# motors.net
KiCad netlist of a schematic drawn in EAGLE
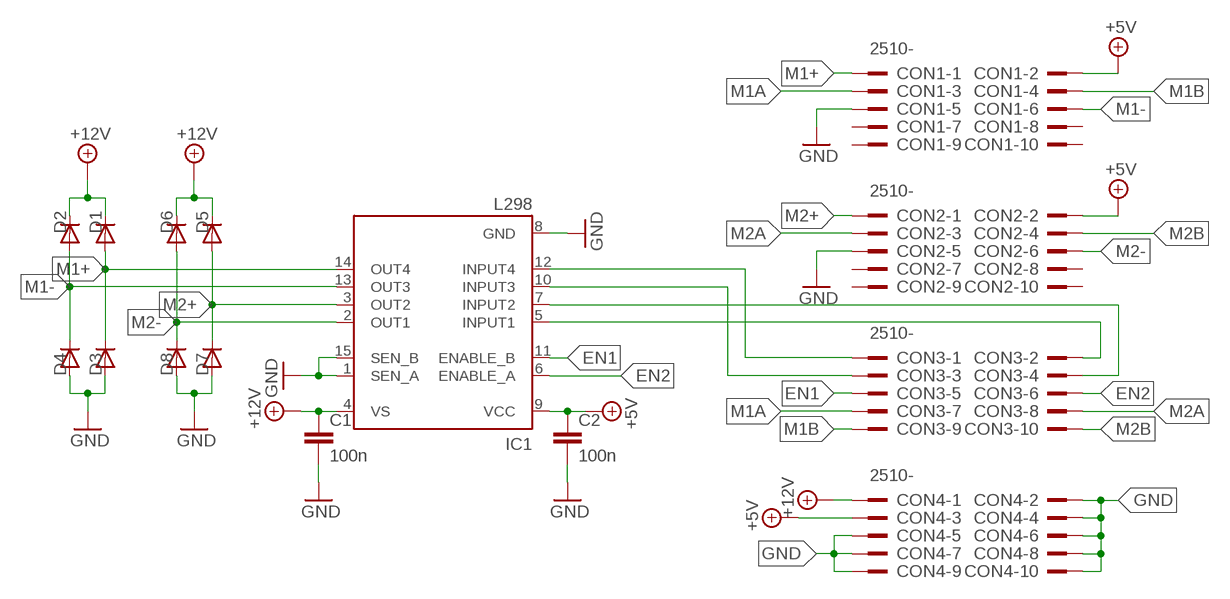
[diagram p0: schematic, sheet 1]

(export (version "E")
  (design (tool "Eeschema 10.0.6"))
  (components
    (comp (ref "C1")
      (value "100n")
      (footprint "eagle-import:C050-025X075")
      (libsource (lib "eagle-import") (part "C-EU050-025X075"))
    )
    (comp (ref "C2")
      (value "100n")
      (footprint "eagle-import:C050-025X075")
      (libsource (lib "eagle-import") (part "C-EU050-025X075"))
    )
    (comp (ref "CON1")
      (value "2510-")
      (footprint "eagle-import:PAK100_2500-10")
      (fields (field (name "MF") "3M") (field (name "MPN") "2510-6002UB"))
      (libsource (lib "eagle-import") (part "2510-"))
    )
    (comp (ref "CON2")
      (value "2510-")
      (footprint "eagle-import:PAK100_2500-10")
      (fields (field (name "MF") "3M") (field (name "MPN") "2510-6002UB"))
      (libsource (lib "eagle-import") (part "2510-"))
    )
    (comp (ref "CON3")
      (value "2510-")
      (footprint "eagle-import:PAK100_2500-10")
      (fields (field (name "MF") "3M") (field (name "MPN") "2510-6002UB"))
      (libsource (lib "eagle-import") (part "2510-"))
    )
    (comp (ref "CON4")
      (value "2510-")
      (footprint "eagle-import:PAK100_2500-10")
      (fields (field (name "MF") "3M") (field (name "MPN") "2510-6002UB"))
      (libsource (lib "eagle-import") (part "2510-"))
    )
    (comp (ref "D1")
      (value "1N4004")
      (footprint "eagle-import:DO41-10")
      (libsource (lib "eagle-import") (part "1N4004"))
    )
    (comp (ref "D2")
      (value "1N4004")
      (footprint "eagle-import:DO41-10")
      (libsource (lib "eagle-import") (part "1N4004"))
    )
    (comp (ref "D3")
      (value "1N4004")
      (footprint "eagle-import:DO41-10")
      (libsource (lib "eagle-import") (part "1N4004"))
    )
    (comp (ref "D4")
      (value "1N4004")
      (footprint "eagle-import:DO41-10")
      (libsource (lib "eagle-import") (part "1N4004"))
    )
    (comp (ref "D5")
      (value "1N4004")
      (footprint "eagle-import:DO41-10")
      (libsource (lib "eagle-import") (part "1N4004"))
    )
    (comp (ref "D6")
      (value "1N4004")
      (footprint "eagle-import:DO41-10")
      (libsource (lib "eagle-import") (part "1N4004"))
    )
    (comp (ref "D7")
      (value "1N4004")
      (footprint "eagle-import:DO41-10")
      (libsource (lib "eagle-import") (part "1N4004"))
    )
    (comp (ref "D8")
      (value "1N4004")
      (footprint "eagle-import:DO41-10")
      (libsource (lib "eagle-import") (part "1N4004"))
    )
    (comp (ref "IC1")
      (value "L298")
      (footprint "eagle-import:MULTIWATT-15")
      (fields (field (name "MPN") "L298N"))
      (libsource (lib "eagle-import") (part "L298"))
    )
  )
  (nets
    (net (code "1") (name "+5V") (class "Default")
      (node (ref "C2") (pin "1") (pinfunction "1_1") (pintype "passive"))
      (node (ref "CON1") (pin "2") (pinfunction "KL_2") (pintype "passive"))
      (node (ref "CON2") (pin "2") (pinfunction "KL_2") (pintype "passive"))
      (node (ref "CON4") (pin "3") (pinfunction "KL_3") (pintype "passive"))
      (node (ref "IC1") (pin "9") (pinfunction "VCC_9") (pintype "power_in"))
    )
    (net (code "2") (name "+12V") (class "Default")
      (node (ref "C1") (pin "1") (pinfunction "1_1") (pintype "passive"))
      (node (ref "CON4") (pin "1") (pinfunction "KL_1") (pintype "passive"))
      (node (ref "D1") (pin "C") (pinfunction "C_C") (pintype "passive"))
      (node (ref "D2") (pin "C") (pinfunction "C_C") (pintype "passive"))
      (node (ref "D5") (pin "C") (pinfunction "C_C") (pintype "passive"))
      (node (ref "D6") (pin "C") (pinfunction "C_C") (pintype "passive"))
      (node (ref "IC1") (pin "4") (pinfunction "VS_4") (pintype "power_in"))
    )
    (net (code "3") (name "EN1") (class "Default")
      (node (ref "CON3") (pin "5") (pinfunction "KL_5") (pintype "passive"))
      (node (ref "IC1") (pin "11") (pinfunction "ENABLE_B_11") (pintype "input"))
    )
    (net (code "4") (name "EN2") (class "Default")
      (node (ref "CON3") (pin "6") (pinfunction "KL_6") (pintype "passive"))
      (node (ref "IC1") (pin "6") (pinfunction "ENABLE_A_6") (pintype "input"))
    )
    (net (code "5") (name "GND") (class "Default")
      (node (ref "C1") (pin "2") (pinfunction "2_2") (pintype "passive"))
      (node (ref "C2") (pin "2") (pinfunction "2_2") (pintype "passive"))
      (node (ref "CON1") (pin "5") (pinfunction "KL_5") (pintype "passive"))
      (node (ref "CON2") (pin "5") (pinfunction "KL_5") (pintype "passive"))
      (node (ref "CON4") (pin "10") (pinfunction "KL_10") (pintype "passive"))
      (node (ref "CON4") (pin "2") (pinfunction "KL_2") (pintype "passive"))
      (node (ref "CON4") (pin "4") (pinfunction "KL_4") (pintype "passive"))
      (node (ref "CON4") (pin "5") (pinfunction "KL_5") (pintype "passive"))
      (node (ref "CON4") (pin "6") (pinfunction "KL_6") (pintype "passive"))
      (node (ref "CON4") (pin "7") (pinfunction "KL_7") (pintype "passive"))
      (node (ref "CON4") (pin "8") (pinfunction "KL_8") (pintype "passive"))
      (node (ref "CON4") (pin "9") (pinfunction "KL_9") (pintype "passive"))
      (node (ref "D3") (pin "A") (pinfunction "A_A") (pintype "passive"))
      (node (ref "D4") (pin "A") (pinfunction "A_A") (pintype "passive"))
      (node (ref "D7") (pin "A") (pinfunction "A_A") (pintype "passive"))
      (node (ref "D8") (pin "A") (pinfunction "A_A") (pintype "passive"))
      (node (ref "IC1") (pin "1") (pinfunction "SEN_A_1") (pintype "input"))
      (node (ref "IC1") (pin "15") (pinfunction "SEN_B_15") (pintype "input"))
      (node (ref "IC1") (pin "8") (pinfunction "GND_8") (pintype "power_in"))
    )
    (net (code "6") (name "M1+") (class "Default")
      (node (ref "CON1") (pin "1") (pinfunction "KL_1") (pintype "passive"))
      (node (ref "D1") (pin "A") (pinfunction "A_A") (pintype "passive"))
      (node (ref "D3") (pin "C") (pinfunction "C_C") (pintype "passive"))
      (node (ref "IC1") (pin "14") (pinfunction "OUT4_14") (pintype "output"))
    )
    (net (code "7") (name "M1-") (class "Default")
      (node (ref "CON1") (pin "6") (pinfunction "KL_6") (pintype "passive"))
      (node (ref "D2") (pin "A") (pinfunction "A_A") (pintype "passive"))
      (node (ref "D4") (pin "C") (pinfunction "C_C") (pintype "passive"))
      (node (ref "IC1") (pin "13") (pinfunction "OUT3_13") (pintype "output"))
    )
    (net (code "8") (name "M1A") (class "Default")
      (node (ref "CON1") (pin "3") (pinfunction "KL_3") (pintype "passive"))
      (node (ref "CON3") (pin "7") (pinfunction "KL_7") (pintype "passive"))
    )
    (net (code "9") (name "M1B") (class "Default")
      (node (ref "CON1") (pin "4") (pinfunction "KL_4") (pintype "passive"))
      (node (ref "CON3") (pin "9") (pinfunction "KL_9") (pintype "passive"))
    )
    (net (code "10") (name "M2+") (class "Default")
      (node (ref "CON2") (pin "1") (pinfunction "KL_1") (pintype "passive"))
      (node (ref "D5") (pin "A") (pinfunction "A_A") (pintype "passive"))
      (node (ref "D7") (pin "C") (pinfunction "C_C") (pintype "passive"))
      (node (ref "IC1") (pin "3") (pinfunction "OUT2_3") (pintype "output"))
    )
    (net (code "11") (name "M2-") (class "Default")
      (node (ref "CON2") (pin "6") (pinfunction "KL_6") (pintype "passive"))
      (node (ref "D6") (pin "A") (pinfunction "A_A") (pintype "passive"))
      (node (ref "D8") (pin "C") (pinfunction "C_C") (pintype "passive"))
      (node (ref "IC1") (pin "2") (pinfunction "OUT1_2") (pintype "output"))
    )
    (net (code "12") (name "M2A") (class "Default")
      (node (ref "CON2") (pin "3") (pinfunction "KL_3") (pintype "passive"))
      (node (ref "CON3") (pin "8") (pinfunction "KL_8") (pintype "passive"))
    )
    (net (code "13") (name "M2B") (class "Default")
      (node (ref "CON2") (pin "4") (pinfunction "KL_4") (pintype "passive"))
      (node (ref "CON3") (pin "10") (pinfunction "KL_10") (pintype "passive"))
    )
    (net (code "14") (name "Net-(CON3A-KL)") (class "Default")
      (node (ref "CON3") (pin "1") (pinfunction "KL_1") (pintype "passive"))
      (node (ref "IC1") (pin "12") (pinfunction "INPUT4_12") (pintype "input"))
    )
    (net (code "15") (name "Net-(CON3C-KL)") (class "Default")
      (node (ref "CON3") (pin "2") (pinfunction "KL_2") (pintype "passive"))
      (node (ref "IC1") (pin "5") (pinfunction "INPUT1_5") (pintype "input"))
    )
    (net (code "16") (name "Net-(CON3D-KL)") (class "Default")
      (node (ref "CON3") (pin "3") (pinfunction "KL_3") (pintype "passive"))
      (node (ref "IC1") (pin "10") (pinfunction "INPUT3_10") (pintype "input"))
    )
    (net (code "17") (name "Net-(CON3E-KL)") (class "Default")
      (node (ref "CON3") (pin "4") (pinfunction "KL_4") (pintype "passive"))
      (node (ref "IC1") (pin "7") (pinfunction "INPUT2_7") (pintype "input"))
    )
    (net (code "18") (name "unconnected-(CON1B-KL-Pad10)") (class "Default")
      (node (ref "CON1") (pin "10") (pinfunction "KL_10") (pintype "passive"))
    )
    (net (code "19") (name "unconnected-(CON1H-KL-Pad7)") (class "Default")
      (node (ref "CON1") (pin "7") (pinfunction "KL_7") (pintype "passive"))
    )
    (net (code "20") (name "unconnected-(CON1I-KL-Pad8)") (class "Default")
      (node (ref "CON1") (pin "8") (pinfunction "KL_8") (pintype "passive"))
    )
    (net (code "21") (name "unconnected-(CON1J-KL-Pad9)") (class "Default")
      (node (ref "CON1") (pin "9") (pinfunction "KL_9") (pintype "passive"))
    )
    (net (code "22") (name "unconnected-(CON2B-KL-Pad10)") (class "Default")
      (node (ref "CON2") (pin "10") (pinfunction "KL_10") (pintype "passive"))
    )
    (net (code "23") (name "unconnected-(CON2H-KL-Pad7)") (class "Default")
      (node (ref "CON2") (pin "7") (pinfunction "KL_7") (pintype "passive"))
    )
    (net (code "24") (name "unconnected-(CON2I-KL-Pad8)") (class "Default")
      (node (ref "CON2") (pin "8") (pinfunction "KL_8") (pintype "passive"))
    )
    (net (code "25") (name "unconnected-(CON2J-KL-Pad9)") (class "Default")
      (node (ref "CON2") (pin "9") (pinfunction "KL_9") (pintype "passive"))
    )
  )
)
